# main_board.net
KiCad netlist of a schematic drawn in Altium Designer
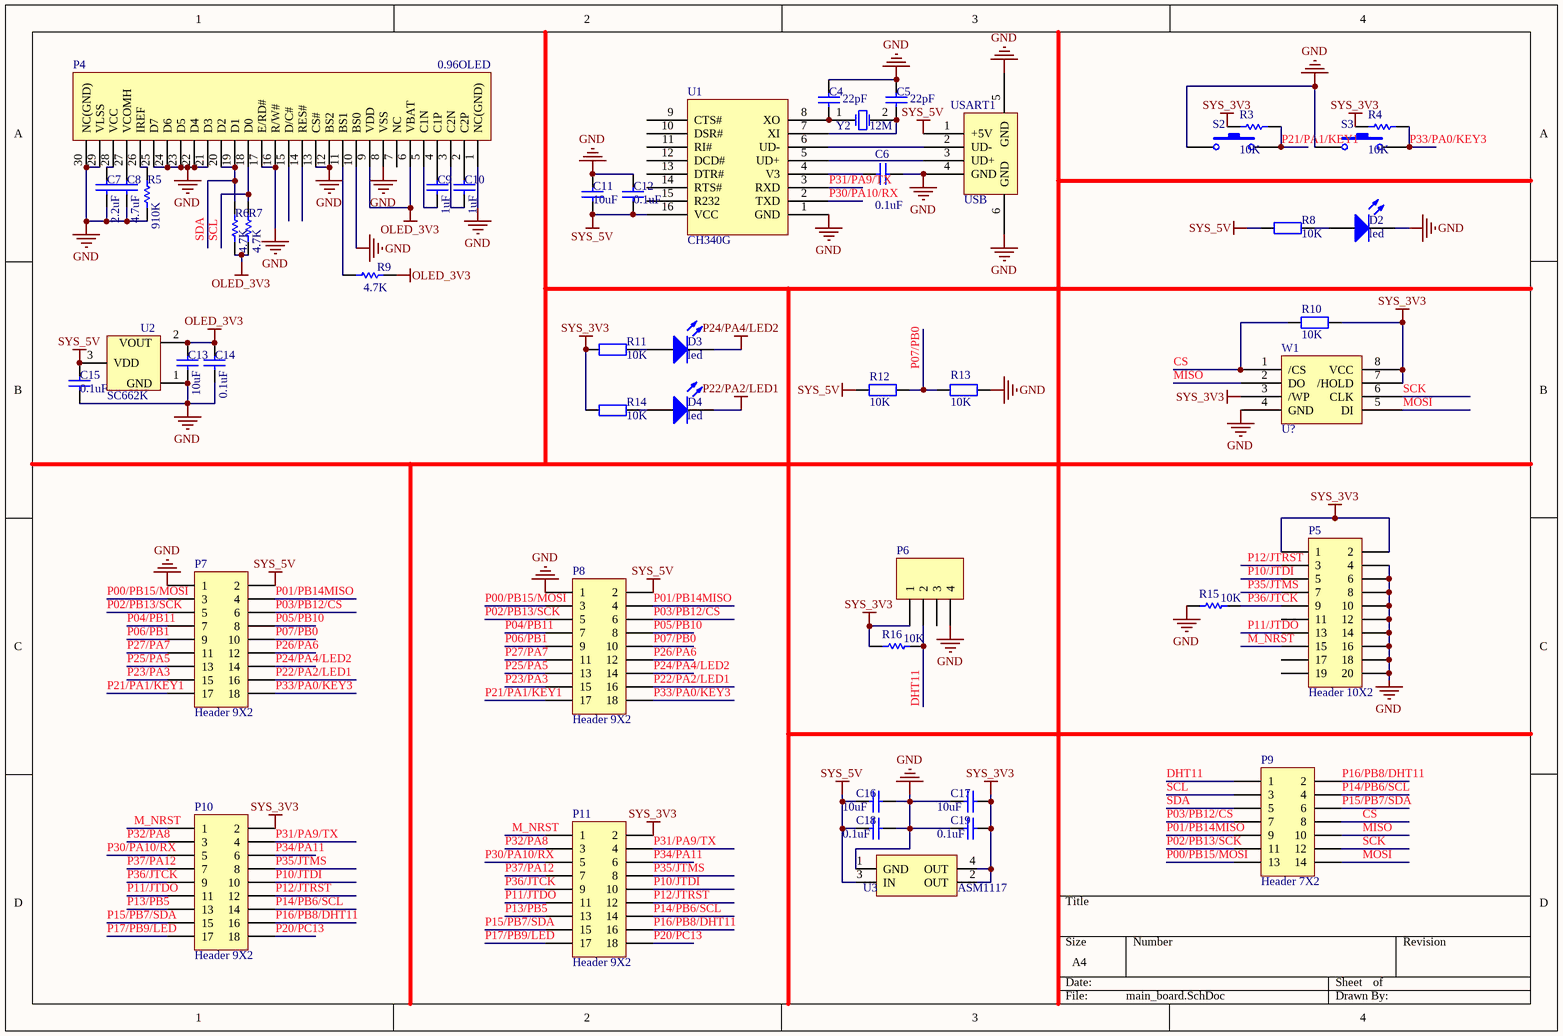
[diagram p0: main_board.SchDoc]

(export (version "E")
  (design (tool "Eeschema 10.0.6"))
  (components
    (comp (ref "C4")
      (value "22pF")
      (footprint "6-0805_N")
      (description "Capacitor")
      (fields (field (name "PUBLISHER") "Altium Limited"))
      (libsource (lib "Miscellaneous Devices") (part "Cap"))
    )
    (comp (ref "C5")
      (value "22pF")
      (footprint "6-0805_N")
      (description "Capacitor")
      (fields (field (name "PUBLISHER") "Altium Limited"))
      (libsource (lib "Miscellaneous Devices") (part "Cap"))
    )
    (comp (ref "C6")
      (value "0.1uF")
      (footprint "6-0805_N")
      (description "Capacitor")
      (fields (field (name "PUBLISHER") "Altium Limited"))
      (libsource (lib "Miscellaneous Devices") (part "Cap"))
    )
    (comp (ref "C7")
      (value "2.2uF")
      (footprint "6-0805_N")
      (description "Capacitor")
      (fields (field (name "PUBLISHER") "Altium Limited"))
      (libsource (lib "Miscellaneous Devices") (part "Cap"))
    )
    (comp (ref "C8")
      (value "4.7uF")
      (footprint "6-0805_N")
      (description "Capacitor")
      (fields (field (name "PUBLISHER") "Altium Limited"))
      (libsource (lib "Miscellaneous Devices") (part "Cap"))
    )
    (comp (ref "C9")
      (value "1uF")
      (footprint "6-0805_N")
      (description "Capacitor")
      (fields (field (name "PUBLISHER") "Altium Limited"))
      (libsource (lib "Miscellaneous Devices") (part "Cap"))
    )
    (comp (ref "C10")
      (value "1uF")
      (footprint "6-0805_N")
      (description "Capacitor")
      (fields (field (name "PUBLISHER") "Altium Limited"))
      (libsource (lib "Miscellaneous Devices") (part "Cap"))
    )
    (comp (ref "C11")
      (value "10uF")
      (footprint "6-0805_N")
      (description "Capacitor")
      (fields (field (name "PUBLISHER") "Altium Limited"))
      (libsource (lib "Miscellaneous Devices") (part "Cap"))
    )
    (comp (ref "C12")
      (value "0.1uF")
      (footprint "6-0805_N")
      (description "Capacitor")
      (fields (field (name "PUBLISHER") "Altium Limited"))
      (libsource (lib "Miscellaneous Devices") (part "Cap"))
    )
    (comp (ref "C13")
      (value "10uF")
      (footprint "6-0805_N")
      (description "Capacitor")
      (fields (field (name "PUBLISHER") "Altium Limited"))
      (libsource (lib "Miscellaneous Devices") (part "Cap"))
    )
    (comp (ref "C14")
      (value "0.1uF")
      (footprint "6-0805_N")
      (description "Capacitor")
      (fields (field (name "PUBLISHER") "Altium Limited"))
      (libsource (lib "Miscellaneous Devices") (part "Cap"))
    )
    (comp (ref "C15")
      (value "0.1uF")
      (footprint "6-0805_N")
      (description "Capacitor")
      (fields (field (name "PUBLISHER") "Altium Limited"))
      (libsource (lib "Miscellaneous Devices") (part "Cap"))
    )
    (comp (ref "C16")
      (value "10uF")
      (footprint "6-0805_N")
      (description "Capacitor")
      (fields (field (name "PUBLISHER") "Altium Limited"))
      (libsource (lib "Miscellaneous Devices") (part "Cap"))
    )
    (comp (ref "C17")
      (value "10uF")
      (footprint "6-0805_N")
      (description "Capacitor")
      (fields (field (name "PUBLISHER") "Altium Limited"))
      (libsource (lib "Miscellaneous Devices") (part "Cap"))
    )
    (comp (ref "C18")
      (value "0.1uF")
      (footprint "6-0805_N")
      (description "Capacitor")
      (fields (field (name "PUBLISHER") "Altium Limited"))
      (libsource (lib "Miscellaneous Devices") (part "Cap"))
    )
    (comp (ref "C19")
      (value "0.1uF")
      (footprint "6-0805_N")
      (description "Capacitor")
      (fields (field (name "PUBLISHER") "Altium Limited"))
      (libsource (lib "Miscellaneous Devices") (part "Cap"))
    )
    (comp (ref "D2")
      (value "led")
      (footprint "LED")
      (description "Typical INFRARED GaAs LED")
      (fields (field (name "PUBLISHER") "Altium Limited"))
      (libsource (lib "Miscellaneous Devices") (part "LED0"))
    )
    (comp (ref "D3")
      (value "led")
      (footprint "LED")
      (description "Typical INFRARED GaAs LED")
      (fields (field (name "PUBLISHER") "Altium Limited"))
      (libsource (lib "Miscellaneous Devices") (part "LED0"))
    )
    (comp (ref "D4")
      (value "led")
      (footprint "LED")
      (description "Typical INFRARED GaAs LED")
      (fields (field (name "PUBLISHER") "Altium Limited"))
      (libsource (lib "Miscellaneous Devices") (part "LED0"))
    )
    (comp (ref "P4")
      (value "0.96OLED")
      (footprint "OLED")
      (description "接口")
      (fields (field (name "PUBLISHER") "Altium Limited"))
      (libsource (lib "HLW8012-Demo") (part "0.96OLED"))
    )
    (comp (ref "P5")
      (value "Header 10X2")
      (footprint "JLINK")
      (description "Header, 10-Pin, Dual row")
      (fields (field (name "PUBLISHER") "Altium Limited"))
      (libsource (lib "Miscellaneous Connectors") (part "Header 10X2"))
    )
    (comp (ref "P6")
      (value "~")
      (footprint "DHT11")
      (description "Header, 4-Pin")
      (fields (field (name "PUBLISHER") "Altium Limited"))
      (libsource (lib "Miscellaneous Connectors") (part "Header 4"))
    )
    (comp (ref "P7")
      (value "Header 9X2")
      (footprint "XDR2x9_S")
      (description "Header, 9-Pin, Dual row")
      (fields (field (name "PUBLISHER") "Altium Limited"))
      (libsource (lib "Miscellaneous Connectors") (part "Header 9X2"))
    )
    (comp (ref "P8")
      (value "Header 9X2")
      (footprint "XDR2x9_L_1")
      (description "Header, 9-Pin, Dual row")
      (fields (field (name "PUBLISHER") "Altium Limited"))
      (libsource (lib "Miscellaneous Connectors") (part "Header 9X2"))
    )
    (comp (ref "P9")
      (value "Header 7X2")
      (footprint "XDR2X7")
      (description "Header, 7-Pin, Dual row")
      (fields (field (name "PUBLISHER") "Altium Limited"))
      (libsource (lib "Miscellaneous Connectors") (part "Header 7X2"))
    )
    (comp (ref "P10")
      (value "Header 9X2")
      (footprint "XDR2x9_S")
      (description "Header, 9-Pin, Dual row")
      (fields (field (name "PUBLISHER") "Altium Limited"))
      (libsource (lib "Miscellaneous Connectors") (part "Header 9X2"))
    )
    (comp (ref "P11")
      (value "Header 9X2")
      (footprint "XDR2x9_L_2")
      (description "Header, 9-Pin, Dual row")
      (fields (field (name "PUBLISHER") "Altium Limited"))
      (libsource (lib "Miscellaneous Connectors") (part "Header 9X2"))
    )
    (comp (ref "R3")
      (value "10K")
      (footprint "6-0805_N")
      (description "Resistor")
      (fields (field (name "PUBLISHER") "Altium Limited"))
      (libsource (lib "Miscellaneous Devices") (part "Res1"))
    )
    (comp (ref "R4")
      (value "10K")
      (footprint "6-0805_N")
      (description "Resistor")
      (fields (field (name "PUBLISHER") "Altium Limited"))
      (libsource (lib "Miscellaneous Devices") (part "Res1"))
    )
    (comp (ref "R5")
      (value "910K")
      (footprint "6-0805_N")
      (description "Resistor")
      (fields (field (name "PUBLISHER") "Altium Limited"))
      (libsource (lib "Miscellaneous Devices") (part "Res1"))
    )
    (comp (ref "R6")
      (value "4.7K")
      (footprint "6-0805_N")
      (description "Resistor")
      (fields (field (name "PUBLISHER") "Altium Limited"))
      (libsource (lib "Miscellaneous Devices") (part "Res1"))
    )
    (comp (ref "R7")
      (value "4.7K")
      (footprint "6-0805_N")
      (description "Resistor")
      (fields (field (name "PUBLISHER") "Altium Limited"))
      (libsource (lib "Miscellaneous Devices") (part "Res1"))
    )
    (comp (ref "R8")
      (value "10K")
      (footprint "6-0805_N")
      (description "Resistor")
      (fields (field (name "PUBLISHER") "Altium Limited"))
      (libsource (lib "Miscellaneous Devices") (part "Res2"))
    )
    (comp (ref "R9")
      (value "4.7K")
      (footprint "6-0805_N")
      (description "Resistor")
      (fields (field (name "PUBLISHER") "Altium Limited"))
      (libsource (lib "Miscellaneous Devices") (part "Res1"))
    )
    (comp (ref "R10")
      (value "10K")
      (footprint "6-0805_N")
      (description "Resistor")
      (fields (field (name "PUBLISHER") "Altium Limited"))
      (libsource (lib "") (part "Res2_1"))
    )
    (comp (ref "R11")
      (value "10K")
      (footprint "6-0805_N")
      (description "Resistor")
      (fields (field (name "PUBLISHER") "Altium Limited"))
      (libsource (lib "Miscellaneous Devices") (part "Res2"))
    )
    (comp (ref "R12")
      (value "10K")
      (footprint "6-0805_N")
      (description "Resistor")
      (fields (field (name "PUBLISHER") "Altium Limited"))
      (libsource (lib "") (part "Res2_1"))
    )
    (comp (ref "R13")
      (value "10K")
      (footprint "6-0805_N")
      (description "Resistor")
      (fields (field (name "PUBLISHER") "Altium Limited"))
      (libsource (lib "Miscellaneous Devices") (part "Res2"))
    )
    (comp (ref "R14")
      (value "10K")
      (footprint "6-0805_N")
      (description "Resistor")
      (fields (field (name "PUBLISHER") "Altium Limited"))
      (libsource (lib "Miscellaneous Devices") (part "Res2"))
    )
    (comp (ref "R15")
      (value "10K")
      (footprint "6-0805_N")
      (description "Resistor")
      (fields (field (name "PUBLISHER") "Altium Limited"))
      (libsource (lib "Miscellaneous Devices") (part "Res1"))
    )
    (comp (ref "R16")
      (value "10K")
      (footprint "6-0805_N")
      (description "Resistor")
      (fields (field (name "PUBLISHER") "Altium Limited"))
      (libsource (lib "Miscellaneous Devices") (part "Res1"))
    )
    (comp (ref "S2")
      (value "~")
      (footprint "SPST-2")
      (description "Switch")
      (fields (field (name "PUBLISHER") "Altium Limited"))
      (libsource (lib "Miscellaneous Devices") (part "SW-PB"))
    )
    (comp (ref "S3")
      (value "~")
      (footprint "SPST-2")
      (description "Switch")
      (fields (field (name "PUBLISHER") "Altium Limited"))
      (libsource (lib "Miscellaneous Devices") (part "SW-PB"))
    )
    (comp (ref "U1") (value "CH340G") (footprint "SOP-16") (libsource (lib "Schlib1") (part "CH340G")))
    (comp (ref "U2") (value "SC662K") (footprint "SOP23") (libsource (lib "BalanceCar") (part "SC662K")))
    (comp (ref "U3") (value "ASM1117") (footprint "SOT-223") (libsource (lib "BalanceCar") (part "ASM1117")))
    (comp (ref "USART1") (value "USB") (footprint "USB") (libsource (lib "Schlib1") (part "USB")))
    (comp (ref "W1") (value "U?") (footprint "SO8_N") (libsource (lib "One_Rice_DIY") (part "W25Q16")))
    (comp (ref "Y2")
      (value "12M")
      (footprint "HC-49S")
      (description "Crystal Oscillator")
      (fields (field (name "PUBLISHER") "Altium Limited"))
      (libsource (lib "Miscellaneous Devices") (part "XTAL"))
    )
  )
  (nets
    (net (code "1") (name "/CS") (class "Default")
      (node (ref "P9") (pin "8") (pinfunction "8_8") (pintype "passive"))
      (node (ref "R10") (pin "2") (pinfunction "2_2") (pintype "passive"))
      (node (ref "W1") (pin "1") (pinfunction "/CS_1") (pintype "passive"))
    )
    (net (code "2") (name "/DHT11") (class "Default")
      (node (ref "P6") (pin "2") (pinfunction "2_2") (pintype "passive"))
      (node (ref "P9") (pin "1") (pinfunction "1_1") (pintype "passive"))
      (node (ref "R16") (pin "2") (pinfunction "2_2") (pintype "passive"))
    )
    (net (code "3") (name "/MISO") (class "Default")
      (node (ref "P9") (pin "10") (pinfunction "10_10") (pintype "passive"))
      (node (ref "W1") (pin "2") (pinfunction "DO_2") (pintype "passive"))
    )
    (net (code "4") (name "/MOSI") (class "Default")
      (node (ref "P9") (pin "14") (pinfunction "14_14") (pintype "passive"))
      (node (ref "W1") (pin "5") (pinfunction "DI_5") (pintype "passive"))
    )
    (net (code "5") (name "/M_NRST") (class "Default")
      (node (ref "P10") (pin "1") (pinfunction "1_1") (pintype "passive"))
      (node (ref "P11") (pin "1") (pinfunction "1_1") (pintype "passive"))
      (node (ref "P5") (pin "15") (pinfunction "15_15") (pintype "passive"))
    )
    (net (code "6") (name "/P00{slash}PB15{slash}MOSI") (class "Default")
      (node (ref "P7") (pin "3") (pinfunction "3_3") (pintype "passive"))
      (node (ref "P8") (pin "3") (pinfunction "3_3") (pintype "passive"))
      (node (ref "P9") (pin "13") (pinfunction "13_13") (pintype "passive"))
    )
    (net (code "7") (name "/P01{slash}PB14MISO") (class "Default")
      (node (ref "P7") (pin "4") (pinfunction "4_4") (pintype "passive"))
      (node (ref "P8") (pin "4") (pinfunction "4_4") (pintype "passive"))
      (node (ref "P9") (pin "9") (pinfunction "9_9") (pintype "passive"))
    )
    (net (code "8") (name "/P02{slash}PB13{slash}SCK") (class "Default")
      (node (ref "P7") (pin "5") (pinfunction "5_5") (pintype "passive"))
      (node (ref "P8") (pin "5") (pinfunction "5_5") (pintype "passive"))
      (node (ref "P9") (pin "11") (pinfunction "11_11") (pintype "passive"))
    )
    (net (code "9") (name "/P03{slash}PB12{slash}CS") (class "Default")
      (node (ref "P7") (pin "6") (pinfunction "6_6") (pintype "passive"))
      (node (ref "P8") (pin "6") (pinfunction "6_6") (pintype "passive"))
      (node (ref "P9") (pin "7") (pinfunction "7_7") (pintype "passive"))
    )
    (net (code "10") (name "/P04{slash}PB11") (class "Default")
      (node (ref "P7") (pin "7") (pinfunction "7_7") (pintype "passive"))
      (node (ref "P8") (pin "7") (pinfunction "7_7") (pintype "passive"))
    )
    (net (code "11") (name "/P05{slash}PB10") (class "Default")
      (node (ref "P7") (pin "8") (pinfunction "8_8") (pintype "passive"))
      (node (ref "P8") (pin "8") (pinfunction "8_8") (pintype "passive"))
    )
    (net (code "12") (name "/P06{slash}PB1") (class "Default")
      (node (ref "P7") (pin "9") (pinfunction "9_9") (pintype "passive"))
      (node (ref "P8") (pin "9") (pinfunction "9_9") (pintype "passive"))
    )
    (net (code "13") (name "/P07{slash}PB0") (class "Default")
      (node (ref "P7") (pin "10") (pinfunction "10_10") (pintype "passive"))
      (node (ref "P8") (pin "10") (pinfunction "10_10") (pintype "passive"))
      (node (ref "R12") (pin "1") (pinfunction "1_1") (pintype "passive"))
      (node (ref "R13") (pin "1") (pinfunction "1_1") (pintype "passive"))
    )
    (net (code "14") (name "/P10{slash}JTDI") (class "Default")
      (node (ref "P10") (pin "10") (pinfunction "10_10") (pintype "passive"))
      (node (ref "P11") (pin "10") (pinfunction "10_10") (pintype "passive"))
      (node (ref "P5") (pin "5") (pinfunction "5_5") (pintype "passive"))
    )
    (net (code "15") (name "/P11{slash}JTDO") (class "Default")
      (node (ref "P10") (pin "11") (pinfunction "11_11") (pintype "passive"))
      (node (ref "P11") (pin "11") (pinfunction "11_11") (pintype "passive"))
      (node (ref "P5") (pin "13") (pinfunction "13_13") (pintype "passive"))
    )
    (net (code "16") (name "/P12{slash}JTRST") (class "Default")
      (node (ref "P10") (pin "12") (pinfunction "12_12") (pintype "passive"))
      (node (ref "P11") (pin "12") (pinfunction "12_12") (pintype "passive"))
      (node (ref "P5") (pin "3") (pinfunction "3_3") (pintype "passive"))
    )
    (net (code "17") (name "/P13{slash}PB5") (class "Default")
      (node (ref "P10") (pin "13") (pinfunction "13_13") (pintype "passive"))
      (node (ref "P11") (pin "13") (pinfunction "13_13") (pintype "passive"))
    )
    (net (code "18") (name "/P14{slash}PB6{slash}SCL") (class "Default")
      (node (ref "P10") (pin "14") (pinfunction "14_14") (pintype "passive"))
      (node (ref "P11") (pin "14") (pinfunction "14_14") (pintype "passive"))
      (node (ref "P9") (pin "4") (pinfunction "4_4") (pintype "passive"))
    )
    (net (code "19") (name "/P15{slash}PB7{slash}SDA") (class "Default")
      (node (ref "P10") (pin "15") (pinfunction "15_15") (pintype "passive"))
      (node (ref "P11") (pin "15") (pinfunction "15_15") (pintype "passive"))
      (node (ref "P9") (pin "6") (pinfunction "6_6") (pintype "passive"))
    )
    (net (code "20") (name "/P16{slash}PB8{slash}DHT11") (class "Default")
      (node (ref "P10") (pin "16") (pinfunction "16_16") (pintype "passive"))
      (node (ref "P11") (pin "16") (pinfunction "16_16") (pintype "passive"))
      (node (ref "P9") (pin "2") (pinfunction "2_2") (pintype "passive"))
    )
    (net (code "21") (name "/P17{slash}PB9{slash}LED") (class "Default")
      (node (ref "P10") (pin "17") (pinfunction "17_17") (pintype "passive"))
      (node (ref "P11") (pin "17") (pinfunction "17_17") (pintype "passive"))
    )
    (net (code "22") (name "/P20{slash}PC13") (class "Default")
      (node (ref "P10") (pin "18") (pinfunction "18_18") (pintype "passive"))
      (node (ref "P11") (pin "18") (pinfunction "18_18") (pintype "passive"))
    )
    (net (code "23") (name "/P21{slash}PA1{slash}KEY1") (class "Default")
      (node (ref "P7") (pin "17") (pinfunction "17_17") (pintype "passive"))
      (node (ref "P8") (pin "17") (pinfunction "17_17") (pintype "passive"))
      (node (ref "R3") (pin "1") (pinfunction "1_1") (pintype "passive"))
      (node (ref "S2") (pin "2") (pinfunction "2_2") (pintype "passive"))
    )
    (net (code "24") (name "/P23{slash}PA3") (class "Default")
      (node (ref "P7") (pin "15") (pinfunction "15_15") (pintype "passive"))
      (node (ref "P8") (pin "15") (pinfunction "15_15") (pintype "passive"))
    )
    (net (code "25") (name "/P25{slash}PA5") (class "Default")
      (node (ref "P7") (pin "13") (pinfunction "13_13") (pintype "passive"))
      (node (ref "P8") (pin "13") (pinfunction "13_13") (pintype "passive"))
    )
    (net (code "26") (name "/P26{slash}PA6") (class "Default")
      (node (ref "P7") (pin "12") (pinfunction "12_12") (pintype "passive"))
      (node (ref "P8") (pin "12") (pinfunction "12_12") (pintype "passive"))
    )
    (net (code "27") (name "/P27{slash}PA7") (class "Default")
      (node (ref "P7") (pin "11") (pinfunction "11_11") (pintype "passive"))
      (node (ref "P8") (pin "11") (pinfunction "11_11") (pintype "passive"))
    )
    (net (code "28") (name "/P30{slash}PA10{slash}RX") (class "Default")
      (node (ref "P10") (pin "5") (pinfunction "5_5") (pintype "passive"))
      (node (ref "P11") (pin "5") (pinfunction "5_5") (pintype "passive"))
      (node (ref "U1") (pin "2") (pinfunction "TXD_2") (pintype "passive"))
    )
    (net (code "29") (name "/P31{slash}PA9{slash}TX") (class "Default")
      (node (ref "P10") (pin "4") (pinfunction "4_4") (pintype "passive"))
      (node (ref "P11") (pin "4") (pinfunction "4_4") (pintype "passive"))
      (node (ref "U1") (pin "3") (pinfunction "RXD_3") (pintype "passive"))
    )
    (net (code "30") (name "/P32{slash}PA8") (class "Default")
      (node (ref "P10") (pin "3") (pinfunction "3_3") (pintype "passive"))
      (node (ref "P11") (pin "3") (pinfunction "3_3") (pintype "passive"))
    )
    (net (code "31") (name "/P33{slash}PA0{slash}KEY3") (class "Default")
      (node (ref "P7") (pin "18") (pinfunction "18_18") (pintype "passive"))
      (node (ref "P8") (pin "18") (pinfunction "18_18") (pintype "passive"))
      (node (ref "R4") (pin "1") (pinfunction "1_1") (pintype "passive"))
      (node (ref "S3") (pin "2") (pinfunction "2_2") (pintype "passive"))
    )
    (net (code "32") (name "/P34{slash}PA11") (class "Default")
      (node (ref "P10") (pin "6") (pinfunction "6_6") (pintype "passive"))
      (node (ref "P11") (pin "6") (pinfunction "6_6") (pintype "passive"))
    )
    (net (code "33") (name "/P35{slash}JTMS") (class "Default")
      (node (ref "P10") (pin "8") (pinfunction "8_8") (pintype "passive"))
      (node (ref "P11") (pin "8") (pinfunction "8_8") (pintype "passive"))
      (node (ref "P5") (pin "7") (pinfunction "7_7") (pintype "passive"))
    )
    (net (code "34") (name "/P36{slash}JTCK") (class "Default")
      (node (ref "P10") (pin "9") (pinfunction "9_9") (pintype "passive"))
      (node (ref "P11") (pin "9") (pinfunction "9_9") (pintype "passive"))
      (node (ref "P5") (pin "9") (pinfunction "9_9") (pintype "passive"))
      (node (ref "R15") (pin "2") (pinfunction "2_2") (pintype "passive"))
    )
    (net (code "35") (name "/P37{slash}PA12") (class "Default")
      (node (ref "P10") (pin "7") (pinfunction "7_7") (pintype "passive"))
      (node (ref "P11") (pin "7") (pinfunction "7_7") (pintype "passive"))
    )
    (net (code "36") (name "/SCK") (class "Default")
      (node (ref "P9") (pin "12") (pinfunction "12_12") (pintype "passive"))
      (node (ref "W1") (pin "6") (pinfunction "CLK_6") (pintype "passive"))
    )
    (net (code "37") (name "/SCL") (class "Default")
      (node (ref "P4") (pin "18") (pinfunction "D0_18") (pintype "passive"))
      (node (ref "P9") (pin "3") (pinfunction "3_3") (pintype "passive"))
      (node (ref "R7") (pin "1") (pinfunction "1_1") (pintype "passive"))
    )
    (net (code "38") (name "/SDA") (class "Default")
      (node (ref "P4") (pin "19") (pinfunction "D1_19") (pintype "passive"))
      (node (ref "P4") (pin "20") (pinfunction "D2_20") (pintype "passive"))
      (node (ref "P9") (pin "5") (pinfunction "5_5") (pintype "passive"))
      (node (ref "R6") (pin "1") (pinfunction "1_1") (pintype "passive"))
    )
    (net (code "39") (name "GND") (class "Default")
      (node (ref "C11") (pin "1") (pinfunction "1_1") (pintype "passive"))
      (node (ref "C12") (pin "1") (pinfunction "1_1") (pintype "passive"))
      (node (ref "C13") (pin "1") (pinfunction "1_1") (pintype "passive"))
      (node (ref "C14") (pin "1") (pinfunction "1_1") (pintype "passive"))
      (node (ref "C15") (pin "1") (pinfunction "1_1") (pintype "passive"))
      (node (ref "C16") (pin "2") (pinfunction "2_2") (pintype "passive"))
      (node (ref "C17") (pin "1") (pinfunction "1_1") (pintype "passive"))
      (node (ref "C18") (pin "2") (pinfunction "2_2") (pintype "passive"))
      (node (ref "C19") (pin "1") (pinfunction "1_1") (pintype "passive"))
      (node (ref "C4") (pin "1") (pinfunction "1_1") (pintype "passive"))
      (node (ref "C5") (pin "1") (pinfunction "1_1") (pintype "passive"))
      (node (ref "C6") (pin "1") (pinfunction "1_1") (pintype "passive"))
      (node (ref "C7") (pin "1") (pinfunction "1_1") (pintype "passive"))
      (node (ref "C8") (pin "1") (pinfunction "1_1") (pintype "passive"))
      (node (ref "D2") (pin "2") (pinfunction "K_2") (pintype "passive"))
      (node (ref "P4") (pin "1") (pinfunction "NC(GND)_1") (pintype "passive"))
      (node (ref "P4") (pin "10") (pinfunction "BS0_10") (pintype "passive"))
      (node (ref "P4") (pin "12") (pinfunction "BS2_12") (pintype "passive"))
      (node (ref "P4") (pin "13") (pinfunction "CS#_13") (pintype "passive"))
      (node (ref "P4") (pin "16") (pinfunction "R/W#_16") (pintype "passive"))
      (node (ref "P4") (pin "17") (pinfunction "E/RD#_17") (pintype "passive"))
      (node (ref "P4") (pin "21") (pinfunction "D3_21") (pintype "passive"))
      (node (ref "P4") (pin "22") (pinfunction "D4_22") (pintype "passive"))
      (node (ref "P4") (pin "23") (pinfunction "D5_23") (pintype "passive"))
      (node (ref "P4") (pin "24") (pinfunction "D6_24") (pintype "passive"))
      (node (ref "P4") (pin "25") (pinfunction "D7_25") (pintype "passive"))
      (node (ref "P4") (pin "29") (pinfunction "VLSS_29") (pintype "passive"))
      (node (ref "P4") (pin "30") (pinfunction "NC(GND)_30") (pintype "passive"))
      (node (ref "P4") (pin "8") (pinfunction "VSS_8") (pintype "passive"))
      (node (ref "P5") (pin "10") (pinfunction "10_10") (pintype "passive"))
      (node (ref "P5") (pin "12") (pinfunction "12_12") (pintype "passive"))
      (node (ref "P5") (pin "14") (pinfunction "14_14") (pintype "passive"))
      (node (ref "P5") (pin "16") (pinfunction "16_16") (pintype "passive"))
      (node (ref "P5") (pin "18") (pinfunction "18_18") (pintype "passive"))
      (node (ref "P5") (pin "20") (pinfunction "20_20") (pintype "passive"))
      (node (ref "P5") (pin "4") (pinfunction "4_4") (pintype "passive"))
      (node (ref "P5") (pin "6") (pinfunction "6_6") (pintype "passive"))
      (node (ref "P5") (pin "8") (pinfunction "8_8") (pintype "passive"))
      (node (ref "P6") (pin "4") (pinfunction "4_4") (pintype "passive"))
      (node (ref "P7") (pin "1") (pinfunction "1_1") (pintype "passive"))
      (node (ref "P8") (pin "1") (pinfunction "1_1") (pintype "passive"))
      (node (ref "R13") (pin "2") (pinfunction "2_2") (pintype "passive"))
      (node (ref "R15") (pin "1") (pinfunction "1_1") (pintype "passive"))
      (node (ref "R5") (pin "2") (pinfunction "2_2") (pintype "passive"))
      (node (ref "S2") (pin "1") (pinfunction "1_1") (pintype "passive"))
      (node (ref "S3") (pin "1") (pinfunction "1_1") (pintype "passive"))
      (node (ref "U1") (pin "1") (pinfunction "GND_1") (pintype "passive"))
      (node (ref "U2") (pin "1") (pinfunction "GND_1") (pintype "passive"))
      (node (ref "U3") (pin "1") (pinfunction "GND_1") (pintype "passive"))
      (node (ref "USART1") (pin "4") (pinfunction "GND_4") (pintype "passive"))
      (node (ref "USART1") (pin "5") (pinfunction "GND_5") (pintype "passive"))
      (node (ref "USART1") (pin "6") (pinfunction "GND_6") (pintype "passive"))
      (node (ref "W1") (pin "4") (pinfunction "GND_4") (pintype "passive"))
    )
    (net (code "40") (name "Net-(D2-A)") (class "Default")
      (node (ref "D2") (pin "1") (pinfunction "A_1") (pintype "passive"))
      (node (ref "R8") (pin "2") (pinfunction "2_2") (pintype "passive"))
    )
    (net (code "41") (name "Net-(D3-A)") (class "Default")
      (node (ref "D3") (pin "1") (pinfunction "A_1") (pintype "passive"))
      (node (ref "R11") (pin "2") (pinfunction "2_2") (pintype "passive"))
    )
    (net (code "42") (name "Net-(D4-A)") (class "Default")
      (node (ref "D4") (pin "1") (pinfunction "A_1") (pintype "passive"))
      (node (ref "R14") (pin "2") (pinfunction "2_2") (pintype "passive"))
    )
    (net (code "43") (name "Net-(P4-BS1)") (class "Default")
      (node (ref "P4") (pin "11") (pinfunction "BS1_11") (pintype "passive"))
      (node (ref "R9") (pin "1") (pinfunction "1_1") (pintype "passive"))
    )
    (net (code "44") (name "Net-(P4-C1N)") (class "Default")
      (node (ref "C9") (pin "1") (pinfunction "1_1") (pintype "passive"))
      (node (ref "P4") (pin "5") (pinfunction "C1N_5") (pintype "passive"))
    )
    (net (code "45") (name "Net-(P4-C1P)") (class "Default")
      (node (ref "C9") (pin "2") (pinfunction "2_2") (pintype "passive"))
      (node (ref "P4") (pin "4") (pinfunction "C1P_4") (pintype "passive"))
    )
    (net (code "46") (name "Net-(P4-C2N)") (class "Default")
      (node (ref "C10") (pin "1") (pinfunction "1_1") (pintype "passive"))
      (node (ref "P4") (pin "3") (pinfunction "C2N_3") (pintype "passive"))
    )
    (net (code "47") (name "Net-(P4-C2P)") (class "Default")
      (node (ref "C10") (pin "2") (pinfunction "2_2") (pintype "passive"))
      (node (ref "P4") (pin "2") (pinfunction "C2P_2") (pintype "passive"))
    )
    (net (code "48") (name "Net-(P4-IREF)") (class "Default")
      (node (ref "P4") (pin "26") (pinfunction "IREF_26") (pintype "passive"))
      (node (ref "R5") (pin "1") (pinfunction "1_1") (pintype "passive"))
    )
    (net (code "49") (name "Net-(P4-VCC)") (class "Default")
      (node (ref "C7") (pin "2") (pinfunction "2_2") (pintype "passive"))
      (node (ref "P4") (pin "28") (pinfunction "VCC_28") (pintype "passive"))
    )
    (net (code "50") (name "Net-(P4-VCOMH)") (class "Default")
      (node (ref "C8") (pin "2") (pinfunction "2_2") (pintype "passive"))
      (node (ref "P4") (pin "27") (pinfunction "VCOMH_27") (pintype "passive"))
    )
    (net (code "51") (name "Net-(U1-UD+)") (class "Default")
      (node (ref "U1") (pin "5") (pinfunction "UD+_5") (pintype "passive"))
      (node (ref "USART1") (pin "3") (pinfunction "UD+_3") (pintype "passive"))
    )
    (net (code "52") (name "Net-(U1-UD-)") (class "Default")
      (node (ref "U1") (pin "6") (pinfunction "UD-_6") (pintype "passive"))
      (node (ref "USART1") (pin "2") (pinfunction "UD-_2") (pintype "passive"))
    )
    (net (code "53") (name "Net-(U1-V3)") (class "Default")
      (node (ref "C6") (pin "2") (pinfunction "2_2") (pintype "passive"))
      (node (ref "U1") (pin "4") (pinfunction "V3_4") (pintype "passive"))
    )
    (net (code "54") (name "Net-(U1-XI)") (class "Default")
      (node (ref "C5") (pin "2") (pinfunction "2_2") (pintype "passive"))
      (node (ref "U1") (pin "7") (pinfunction "XI_7") (pintype "passive"))
      (node (ref "Y2") (pin "2") (pinfunction "OSC2_2") (pintype "passive"))
    )
    (net (code "55") (name "Net-(U1-XO)") (class "Default")
      (node (ref "C4") (pin "2") (pinfunction "2_2") (pintype "passive"))
      (node (ref "U1") (pin "8") (pinfunction "XO_8") (pintype "passive"))
      (node (ref "Y2") (pin "1") (pinfunction "OSC1_1") (pintype "passive"))
    )
    (net (code "56") (name "OLED_3V3") (class "Default")
      (node (ref "C13") (pin "2") (pinfunction "2_2") (pintype "passive"))
      (node (ref "C14") (pin "2") (pinfunction "2_2") (pintype "passive"))
      (node (ref "P4") (pin "6") (pinfunction "VBAT_6") (pintype "passive"))
      (node (ref "P4") (pin "9") (pinfunction "VDD_9") (pintype "passive"))
      (node (ref "R6") (pin "2") (pinfunction "2_2") (pintype "passive"))
      (node (ref "R7") (pin "2") (pinfunction "2_2") (pintype "passive"))
      (node (ref "R9") (pin "2") (pinfunction "2_2") (pintype "passive"))
      (node (ref "U2") (pin "2") (pinfunction "VOUT_2") (pintype "passive"))
    )
    (net (code "57") (name "P22{slash}PA2{slash}LED1") (class "Default")
      (node (ref "D4") (pin "2") (pinfunction "K_2") (pintype "passive"))
      (node (ref "P7") (pin "16") (pinfunction "16_16") (pintype "passive"))
      (node (ref "P8") (pin "16") (pinfunction "16_16") (pintype "passive"))
    )
    (net (code "58") (name "P24{slash}PA4{slash}LED2") (class "Default")
      (node (ref "D3") (pin "2") (pinfunction "K_2") (pintype "passive"))
      (node (ref "P7") (pin "14") (pinfunction "14_14") (pintype "passive"))
      (node (ref "P8") (pin "14") (pinfunction "14_14") (pintype "passive"))
    )
    (net (code "59") (name "SYS_3V3") (class "Default")
      (node (ref "C17") (pin "2") (pinfunction "2_2") (pintype "passive"))
      (node (ref "C19") (pin "2") (pinfunction "2_2") (pintype "passive"))
      (node (ref "P10") (pin "2") (pinfunction "2_2") (pintype "passive"))
      (node (ref "P11") (pin "2") (pinfunction "2_2") (pintype "passive"))
      (node (ref "P5") (pin "1") (pinfunction "1_1") (pintype "passive"))
      (node (ref "P5") (pin "2") (pinfunction "2_2") (pintype "passive"))
      (node (ref "P6") (pin "1") (pinfunction "1_1") (pintype "passive"))
      (node (ref "R10") (pin "1") (pinfunction "1_1") (pintype "passive"))
      (node (ref "R11") (pin "1") (pinfunction "1_1") (pintype "passive"))
      (node (ref "R14") (pin "1") (pinfunction "1_1") (pintype "passive"))
      (node (ref "R16") (pin "1") (pinfunction "1_1") (pintype "passive"))
      (node (ref "R3") (pin "2") (pinfunction "2_2") (pintype "passive"))
      (node (ref "R4") (pin "2") (pinfunction "2_2") (pintype "passive"))
      (node (ref "U3") (pin "2") (pinfunction "OUT_2") (pintype "passive"))
      (node (ref "U3") (pin "4") (pinfunction "OUT_4") (pintype "passive"))
      (node (ref "W1") (pin "3") (pinfunction "/WP_3") (pintype "passive"))
      (node (ref "W1") (pin "7") (pinfunction "/HOLD_7") (pintype "passive"))
      (node (ref "W1") (pin "8") (pinfunction "VCC_8") (pintype "passive"))
    )
    (net (code "60") (name "SYS_5V") (class "Default")
      (node (ref "C11") (pin "2") (pinfunction "2_2") (pintype "passive"))
      (node (ref "C12") (pin "2") (pinfunction "2_2") (pintype "passive"))
      (node (ref "C15") (pin "2") (pinfunction "2_2") (pintype "passive"))
      (node (ref "C16") (pin "1") (pinfunction "1_1") (pintype "passive"))
      (node (ref "C18") (pin "1") (pinfunction "1_1") (pintype "passive"))
      (node (ref "P7") (pin "2") (pinfunction "2_2") (pintype "passive"))
      (node (ref "P8") (pin "2") (pinfunction "2_2") (pintype "passive"))
      (node (ref "R12") (pin "2") (pinfunction "2_2") (pintype "passive"))
      (node (ref "R8") (pin "1") (pinfunction "1_1") (pintype "passive"))
      (node (ref "U1") (pin "16") (pinfunction "VCC_16") (pintype "passive"))
      (node (ref "U2") (pin "3") (pinfunction "VDD_3") (pintype "passive"))
      (node (ref "U3") (pin "3") (pinfunction "IN_3") (pintype "passive"))
      (node (ref "USART1") (pin "1") (pinfunction "+5V_1") (pintype "passive"))
    )
    (net (code "61") (name "unconnected-(P4-D{slash}C#-Pad15)") (class "Default")
      (node (ref "P4") (pin "15") (pinfunction "D/C#_15") (pintype "passive"))
    )
    (net (code "62") (name "unconnected-(P4-NC-Pad7)") (class "Default")
      (node (ref "P4") (pin "7") (pinfunction "NC_7") (pintype "passive"))
    )
    (net (code "63") (name "unconnected-(P4-RES#-Pad14)") (class "Default")
      (node (ref "P4") (pin "14") (pinfunction "RES#_14") (pintype "passive"))
    )
    (net (code "64") (name "unconnected-(P5-Pad11)") (class "Default")
      (node (ref "P5") (pin "11") (pinfunction "11_11") (pintype "passive"))
    )
    (net (code "65") (name "unconnected-(P5-Pad17)") (class "Default")
      (node (ref "P5") (pin "17") (pinfunction "17_17") (pintype "passive"))
    )
    (net (code "66") (name "unconnected-(P5-Pad19)") (class "Default")
      (node (ref "P5") (pin "19") (pinfunction "19_19") (pintype "passive"))
    )
    (net (code "67") (name "unconnected-(P6-Pad3)") (class "Default")
      (node (ref "P6") (pin "3") (pinfunction "3_3") (pintype "passive"))
    )
    (net (code "68") (name "unconnected-(U1-CTS#-Pad9)") (class "Default")
      (node (ref "U1") (pin "9") (pinfunction "CTS#_9") (pintype "passive"))
    )
    (net (code "69") (name "unconnected-(U1-DCD#-Pad12)") (class "Default")
      (node (ref "U1") (pin "12") (pinfunction "DCD#_12") (pintype "passive"))
    )
    (net (code "70") (name "unconnected-(U1-DSR#-Pad10)") (class "Default")
      (node (ref "U1") (pin "10") (pinfunction "DSR#_10") (pintype "passive"))
    )
    (net (code "71") (name "unconnected-(U1-DTR#-Pad13)") (class "Default")
      (node (ref "U1") (pin "13") (pinfunction "DTR#_13") (pintype "passive"))
    )
    (net (code "72") (name "unconnected-(U1-R232-Pad15)") (class "Default")
      (node (ref "U1") (pin "15") (pinfunction "R232_15") (pintype "passive"))
    )
    (net (code "73") (name "unconnected-(U1-RI#-Pad11)") (class "Default")
      (node (ref "U1") (pin "11") (pinfunction "RI#_11") (pintype "passive"))
    )
    (net (code "74") (name "unconnected-(U1-RTS#-Pad14)") (class "Default")
      (node (ref "U1") (pin "14") (pinfunction "RTS#_14") (pintype "passive"))
    )
  )
)
